# BGA_LEDs_A.net
KiCad netlist of a schematic drawn in Altium Designer
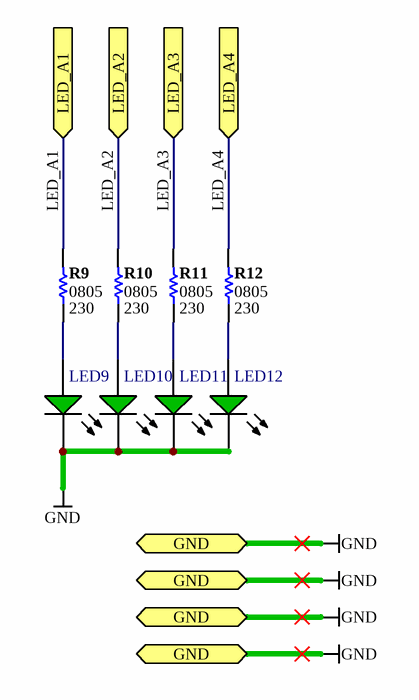
[diagram p0: BGA LEDs A.SchDoc]

(export (version "E")
  (design (tool "Eeschema 10.0.6"))
  (components
    (comp (ref "LED9")
      (value "LED_1206")
      (footprint "RESC0805(2012)70_L")
      (description "GREEN color, 1206, SMD")
      (libsource (lib "Component_DB") (part "LED_GREEN_A1K2-2.A1"))
    )
    (comp (ref "LED10")
      (value "LED_1206")
      (footprint "RESC0805(2012)70_L")
      (description "GREEN color, 1206, SMD")
      (libsource (lib "Component_DB") (part "LED_GREEN_A1K2-2.A1"))
    )
    (comp (ref "LED11")
      (value "LED_1206")
      (footprint "RESC0805(2012)70_L")
      (description "GREEN color, 1206, SMD")
      (libsource (lib "Component_DB") (part "LED_GREEN_A1K2-2.A1"))
    )
    (comp (ref "LED12")
      (value "LED_1206")
      (footprint "RESC0805(2012)70_L")
      (description "GREEN color, 1206, SMD")
      (libsource (lib "Component_DB") (part "LED_GREEN_A1K2-2.A1"))
    )
    (comp (ref "R9")
      (value "0805")
      (footprint "RESC0805(2012)70_L")
      (description "Jumper 0805 (2012 Metric)")
      (fields (field (name "VALUE (OHMS)") "230") (field (name "POWER") "None"))
      (libsource (lib "Component_DB") (part "RES"))
    )
    (comp (ref "R10")
      (value "0805")
      (footprint "RESC0805(2012)70_L")
      (description "Jumper 0805 (2012 Metric)")
      (fields (field (name "VALUE (OHMS)") "230") (field (name "POWER") "None"))
      (libsource (lib "Component_DB") (part "RES"))
    )
    (comp (ref "R11")
      (value "0805")
      (footprint "RESC0805(2012)70_L")
      (description "Jumper 0805 (2012 Metric)")
      (fields (field (name "VALUE (OHMS)") "230") (field (name "POWER") "None"))
      (libsource (lib "Component_DB") (part "RES"))
    )
    (comp (ref "R12")
      (value "0805")
      (footprint "RESC0805(2012)70_L")
      (description "Jumper 0805 (2012 Metric)")
      (fields (field (name "VALUE (OHMS)") "230") (field (name "POWER") "None"))
      (libsource (lib "Component_DB") (part "RES"))
    )
  )
  (nets
    (net (code "1") (name "/LED_A1") (class "Default")
      (node (ref "R9") (pin "2") (pinfunction "2_2") (pintype "passive"))
    )
    (net (code "2") (name "/LED_A2") (class "Default")
      (node (ref "R10") (pin "2") (pinfunction "2_2") (pintype "passive"))
    )
    (net (code "3") (name "/LED_A3") (class "Default")
      (node (ref "R11") (pin "2") (pinfunction "2_2") (pintype "passive"))
    )
    (net (code "4") (name "/LED_A4") (class "Default")
      (node (ref "R12") (pin "2") (pinfunction "2_2") (pintype "passive"))
    )
    (net (code "5") (name "GND") (class "Default")
      (node (ref "LED10") (pin "2") (pinfunction "K_2") (pintype "passive"))
      (node (ref "LED11") (pin "2") (pinfunction "K_2") (pintype "passive"))
      (node (ref "LED12") (pin "2") (pinfunction "K_2") (pintype "passive"))
      (node (ref "LED9") (pin "2") (pinfunction "K_2") (pintype "passive"))
    )
    (net (code "6") (name "Net-(LED9-A)") (class "Default")
      (node (ref "LED9") (pin "1") (pinfunction "A_1") (pintype "passive"))
      (node (ref "R9") (pin "1") (pinfunction "1_1") (pintype "passive"))
    )
    (net (code "7") (name "Net-(LED10-A)") (class "Default")
      (node (ref "LED10") (pin "1") (pinfunction "A_1") (pintype "passive"))
      (node (ref "R10") (pin "1") (pinfunction "1_1") (pintype "passive"))
    )
    (net (code "8") (name "Net-(LED11-A)") (class "Default")
      (node (ref "LED11") (pin "1") (pinfunction "A_1") (pintype "passive"))
      (node (ref "R11") (pin "1") (pinfunction "1_1") (pintype "passive"))
    )
    (net (code "9") (name "Net-(LED12-A)") (class "Default")
      (node (ref "LED12") (pin "1") (pinfunction "A_1") (pintype "passive"))
      (node (ref "R12") (pin "1") (pinfunction "1_1") (pintype "passive"))
    )
  )
)
